# TinyCube01.net
KiCad netlist of a schematic drawn in EAGLE
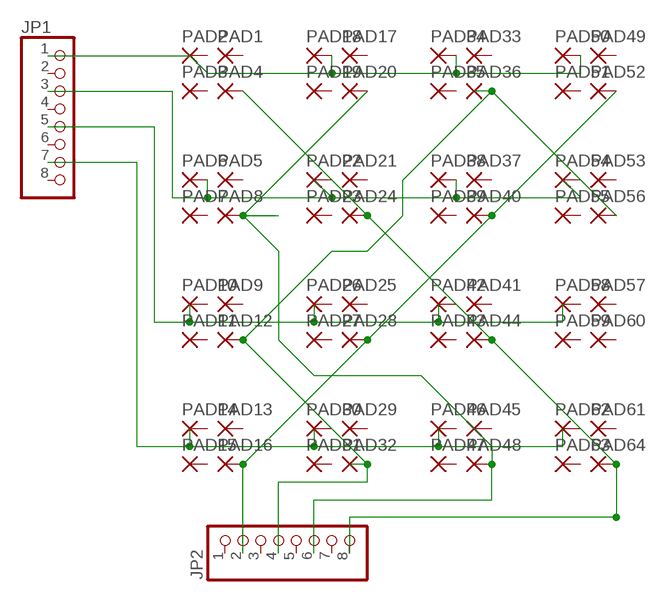
[diagram p0: schematic, sheet 1]

(export (version "E")
  (design (tool "Eeschema 10.0.6"))
  (components
    (comp (ref "JP1")
      (value "PINHD-1X8BIG")
      (footprint "eagle-import:1X08-BIG")
      (libsource (lib "eagle-import") (part "PINHD-1X8BIG"))
    )
    (comp (ref "JP2")
      (value "PINHD-1X8BIG")
      (footprint "eagle-import:1X08-BIG")
      (libsource (lib "eagle-import") (part "PINHD-1X8BIG"))
    )
    (comp (ref "PAD1")
      (value "SMALLPADTHROUGH-HOLE-SMALL")
      (footprint "eagle-import:SMALLPAD")
      (libsource (lib "eagle-import") (part "SMALLPADTHROUGH-HOLE-SMALL"))
    )
    (comp (ref "PAD2")
      (value "SMALLPADTHROUGH-HOLE-SMALL")
      (footprint "eagle-import:SMALLPAD")
      (libsource (lib "eagle-import") (part "SMALLPADTHROUGH-HOLE-SMALL"))
    )
    (comp (ref "PAD3")
      (value "SMALLPADTHROUGH-HOLE-SMALL")
      (footprint "eagle-import:SMALLPAD")
      (libsource (lib "eagle-import") (part "SMALLPADTHROUGH-HOLE-SMALL"))
    )
    (comp (ref "PAD4")
      (value "SMALLPADTHROUGH-HOLE-SMALL")
      (footprint "eagle-import:SMALLPAD")
      (libsource (lib "eagle-import") (part "SMALLPADTHROUGH-HOLE-SMALL"))
    )
    (comp (ref "PAD5")
      (value "SMALLPADTHROUGH-HOLE-SMALL")
      (footprint "eagle-import:SMALLPAD")
      (libsource (lib "eagle-import") (part "SMALLPADTHROUGH-HOLE-SMALL"))
    )
    (comp (ref "PAD6")
      (value "SMALLPADTHROUGH-HOLE-SMALL")
      (footprint "eagle-import:SMALLPAD")
      (libsource (lib "eagle-import") (part "SMALLPADTHROUGH-HOLE-SMALL"))
    )
    (comp (ref "PAD7")
      (value "SMALLPADTHROUGH-HOLE-SMALL")
      (footprint "eagle-import:SMALLPAD")
      (libsource (lib "eagle-import") (part "SMALLPADTHROUGH-HOLE-SMALL"))
    )
    (comp (ref "PAD8")
      (value "SMALLPADTHROUGH-HOLE-SMALL")
      (footprint "eagle-import:SMALLPAD")
      (libsource (lib "eagle-import") (part "SMALLPADTHROUGH-HOLE-SMALL"))
    )
    (comp (ref "PAD9")
      (value "SMALLPADTHROUGH-HOLE-SMALL")
      (footprint "eagle-import:SMALLPAD")
      (libsource (lib "eagle-import") (part "SMALLPADTHROUGH-HOLE-SMALL"))
    )
    (comp (ref "PAD10")
      (value "SMALLPADTHROUGH-HOLE-SMALL")
      (footprint "eagle-import:SMALLPAD")
      (libsource (lib "eagle-import") (part "SMALLPADTHROUGH-HOLE-SMALL"))
    )
    (comp (ref "PAD11")
      (value "SMALLPADTHROUGH-HOLE-SMALL")
      (footprint "eagle-import:SMALLPAD")
      (libsource (lib "eagle-import") (part "SMALLPADTHROUGH-HOLE-SMALL"))
    )
    (comp (ref "PAD12")
      (value "SMALLPADTHROUGH-HOLE-SMALL")
      (footprint "eagle-import:SMALLPAD")
      (libsource (lib "eagle-import") (part "SMALLPADTHROUGH-HOLE-SMALL"))
    )
    (comp (ref "PAD13")
      (value "SMALLPADTHROUGH-HOLE-SMALL")
      (footprint "eagle-import:SMALLPAD")
      (libsource (lib "eagle-import") (part "SMALLPADTHROUGH-HOLE-SMALL"))
    )
    (comp (ref "PAD14")
      (value "SMALLPADTHROUGH-HOLE-SMALL")
      (footprint "eagle-import:SMALLPAD")
      (libsource (lib "eagle-import") (part "SMALLPADTHROUGH-HOLE-SMALL"))
    )
    (comp (ref "PAD15")
      (value "SMALLPADTHROUGH-HOLE-SMALL")
      (footprint "eagle-import:SMALLPAD")
      (libsource (lib "eagle-import") (part "SMALLPADTHROUGH-HOLE-SMALL"))
    )
    (comp (ref "PAD16")
      (value "SMALLPADTHROUGH-HOLE-SMALL")
      (footprint "eagle-import:SMALLPAD")
      (libsource (lib "eagle-import") (part "SMALLPADTHROUGH-HOLE-SMALL"))
    )
    (comp (ref "PAD17")
      (value "SMALLPADTHROUGH-HOLE-SMALL")
      (footprint "eagle-import:SMALLPAD")
      (libsource (lib "eagle-import") (part "SMALLPADTHROUGH-HOLE-SMALL"))
    )
    (comp (ref "PAD18")
      (value "SMALLPADTHROUGH-HOLE-SMALL")
      (footprint "eagle-import:SMALLPAD")
      (libsource (lib "eagle-import") (part "SMALLPADTHROUGH-HOLE-SMALL"))
    )
    (comp (ref "PAD19")
      (value "SMALLPADTHROUGH-HOLE-SMALL")
      (footprint "eagle-import:SMALLPAD")
      (libsource (lib "eagle-import") (part "SMALLPADTHROUGH-HOLE-SMALL"))
    )
    (comp (ref "PAD20")
      (value "SMALLPADTHROUGH-HOLE-SMALL")
      (footprint "eagle-import:SMALLPAD")
      (libsource (lib "eagle-import") (part "SMALLPADTHROUGH-HOLE-SMALL"))
    )
    (comp (ref "PAD21")
      (value "SMALLPADTHROUGH-HOLE-SMALL")
      (footprint "eagle-import:SMALLPAD")
      (libsource (lib "eagle-import") (part "SMALLPADTHROUGH-HOLE-SMALL"))
    )
    (comp (ref "PAD22")
      (value "SMALLPADTHROUGH-HOLE-SMALL")
      (footprint "eagle-import:SMALLPAD")
      (libsource (lib "eagle-import") (part "SMALLPADTHROUGH-HOLE-SMALL"))
    )
    (comp (ref "PAD23")
      (value "SMALLPADTHROUGH-HOLE-SMALL")
      (footprint "eagle-import:SMALLPAD")
      (libsource (lib "eagle-import") (part "SMALLPADTHROUGH-HOLE-SMALL"))
    )
    (comp (ref "PAD24")
      (value "SMALLPADTHROUGH-HOLE-SMALL")
      (footprint "eagle-import:SMALLPAD")
      (libsource (lib "eagle-import") (part "SMALLPADTHROUGH-HOLE-SMALL"))
    )
    (comp (ref "PAD25")
      (value "SMALLPADTHROUGH-HOLE-SMALL")
      (footprint "eagle-import:SMALLPAD")
      (libsource (lib "eagle-import") (part "SMALLPADTHROUGH-HOLE-SMALL"))
    )
    (comp (ref "PAD26")
      (value "SMALLPADTHROUGH-HOLE-SMALL")
      (footprint "eagle-import:SMALLPAD")
      (libsource (lib "eagle-import") (part "SMALLPADTHROUGH-HOLE-SMALL"))
    )
    (comp (ref "PAD27")
      (value "SMALLPADTHROUGH-HOLE-SMALL")
      (footprint "eagle-import:SMALLPAD")
      (libsource (lib "eagle-import") (part "SMALLPADTHROUGH-HOLE-SMALL"))
    )
    (comp (ref "PAD28")
      (value "SMALLPADTHROUGH-HOLE-SMALL")
      (footprint "eagle-import:SMALLPAD")
      (libsource (lib "eagle-import") (part "SMALLPADTHROUGH-HOLE-SMALL"))
    )
    (comp (ref "PAD29")
      (value "SMALLPADTHROUGH-HOLE-SMALL")
      (footprint "eagle-import:SMALLPAD")
      (libsource (lib "eagle-import") (part "SMALLPADTHROUGH-HOLE-SMALL"))
    )
    (comp (ref "PAD30")
      (value "SMALLPADTHROUGH-HOLE-SMALL")
      (footprint "eagle-import:SMALLPAD")
      (libsource (lib "eagle-import") (part "SMALLPADTHROUGH-HOLE-SMALL"))
    )
    (comp (ref "PAD31")
      (value "SMALLPADTHROUGH-HOLE-SMALL")
      (footprint "eagle-import:SMALLPAD")
      (libsource (lib "eagle-import") (part "SMALLPADTHROUGH-HOLE-SMALL"))
    )
    (comp (ref "PAD32")
      (value "SMALLPADTHROUGH-HOLE-SMALL")
      (footprint "eagle-import:SMALLPAD")
      (libsource (lib "eagle-import") (part "SMALLPADTHROUGH-HOLE-SMALL"))
    )
    (comp (ref "PAD33")
      (value "SMALLPADTHROUGH-HOLE-SMALL")
      (footprint "eagle-import:SMALLPAD")
      (libsource (lib "eagle-import") (part "SMALLPADTHROUGH-HOLE-SMALL"))
    )
    (comp (ref "PAD34")
      (value "SMALLPADTHROUGH-HOLE-SMALL")
      (footprint "eagle-import:SMALLPAD")
      (libsource (lib "eagle-import") (part "SMALLPADTHROUGH-HOLE-SMALL"))
    )
    (comp (ref "PAD35")
      (value "SMALLPADTHROUGH-HOLE-SMALL")
      (footprint "eagle-import:SMALLPAD")
      (libsource (lib "eagle-import") (part "SMALLPADTHROUGH-HOLE-SMALL"))
    )
    (comp (ref "PAD36")
      (value "SMALLPADTHROUGH-HOLE-SMALL")
      (footprint "eagle-import:SMALLPAD")
      (libsource (lib "eagle-import") (part "SMALLPADTHROUGH-HOLE-SMALL"))
    )
    (comp (ref "PAD37")
      (value "SMALLPADTHROUGH-HOLE-SMALL")
      (footprint "eagle-import:SMALLPAD")
      (libsource (lib "eagle-import") (part "SMALLPADTHROUGH-HOLE-SMALL"))
    )
    (comp (ref "PAD38")
      (value "SMALLPADTHROUGH-HOLE-SMALL")
      (footprint "eagle-import:SMALLPAD")
      (libsource (lib "eagle-import") (part "SMALLPADTHROUGH-HOLE-SMALL"))
    )
    (comp (ref "PAD39")
      (value "SMALLPADTHROUGH-HOLE-SMALL")
      (footprint "eagle-import:SMALLPAD")
      (libsource (lib "eagle-import") (part "SMALLPADTHROUGH-HOLE-SMALL"))
    )
    (comp (ref "PAD40")
      (value "SMALLPADTHROUGH-HOLE-SMALL")
      (footprint "eagle-import:SMALLPAD")
      (libsource (lib "eagle-import") (part "SMALLPADTHROUGH-HOLE-SMALL"))
    )
    (comp (ref "PAD41")
      (value "SMALLPADTHROUGH-HOLE-SMALL")
      (footprint "eagle-import:SMALLPAD")
      (libsource (lib "eagle-import") (part "SMALLPADTHROUGH-HOLE-SMALL"))
    )
    (comp (ref "PAD42")
      (value "SMALLPADTHROUGH-HOLE-SMALL")
      (footprint "eagle-import:SMALLPAD")
      (libsource (lib "eagle-import") (part "SMALLPADTHROUGH-HOLE-SMALL"))
    )
    (comp (ref "PAD43")
      (value "SMALLPADTHROUGH-HOLE-SMALL")
      (footprint "eagle-import:SMALLPAD")
      (libsource (lib "eagle-import") (part "SMALLPADTHROUGH-HOLE-SMALL"))
    )
    (comp (ref "PAD44")
      (value "SMALLPADTHROUGH-HOLE-SMALL")
      (footprint "eagle-import:SMALLPAD")
      (libsource (lib "eagle-import") (part "SMALLPADTHROUGH-HOLE-SMALL"))
    )
    (comp (ref "PAD45")
      (value "SMALLPADTHROUGH-HOLE-SMALL")
      (footprint "eagle-import:SMALLPAD")
      (libsource (lib "eagle-import") (part "SMALLPADTHROUGH-HOLE-SMALL"))
    )
    (comp (ref "PAD46")
      (value "SMALLPADTHROUGH-HOLE-SMALL")
      (footprint "eagle-import:SMALLPAD")
      (libsource (lib "eagle-import") (part "SMALLPADTHROUGH-HOLE-SMALL"))
    )
    (comp (ref "PAD47")
      (value "SMALLPADTHROUGH-HOLE-SMALL")
      (footprint "eagle-import:SMALLPAD")
      (libsource (lib "eagle-import") (part "SMALLPADTHROUGH-HOLE-SMALL"))
    )
    (comp (ref "PAD48")
      (value "SMALLPADTHROUGH-HOLE-SMALL")
      (footprint "eagle-import:SMALLPAD")
      (libsource (lib "eagle-import") (part "SMALLPADTHROUGH-HOLE-SMALL"))
    )
    (comp (ref "PAD49")
      (value "SMALLPADTHROUGH-HOLE-SMALL")
      (footprint "eagle-import:SMALLPAD")
      (libsource (lib "eagle-import") (part "SMALLPADTHROUGH-HOLE-SMALL"))
    )
    (comp (ref "PAD50")
      (value "SMALLPADTHROUGH-HOLE-SMALL")
      (footprint "eagle-import:SMALLPAD")
      (libsource (lib "eagle-import") (part "SMALLPADTHROUGH-HOLE-SMALL"))
    )
    (comp (ref "PAD51")
      (value "SMALLPADTHROUGH-HOLE-SMALL")
      (footprint "eagle-import:SMALLPAD")
      (libsource (lib "eagle-import") (part "SMALLPADTHROUGH-HOLE-SMALL"))
    )
    (comp (ref "PAD52")
      (value "SMALLPADTHROUGH-HOLE-SMALL")
      (footprint "eagle-import:SMALLPAD")
      (libsource (lib "eagle-import") (part "SMALLPADTHROUGH-HOLE-SMALL"))
    )
    (comp (ref "PAD53")
      (value "SMALLPADTHROUGH-HOLE-SMALL")
      (footprint "eagle-import:SMALLPAD")
      (libsource (lib "eagle-import") (part "SMALLPADTHROUGH-HOLE-SMALL"))
    )
    (comp (ref "PAD54")
      (value "SMALLPADTHROUGH-HOLE-SMALL")
      (footprint "eagle-import:SMALLPAD")
      (libsource (lib "eagle-import") (part "SMALLPADTHROUGH-HOLE-SMALL"))
    )
    (comp (ref "PAD55")
      (value "SMALLPADTHROUGH-HOLE-SMALL")
      (footprint "eagle-import:SMALLPAD")
      (libsource (lib "eagle-import") (part "SMALLPADTHROUGH-HOLE-SMALL"))
    )
    (comp (ref "PAD56")
      (value "SMALLPADTHROUGH-HOLE-SMALL")
      (footprint "eagle-import:SMALLPAD")
      (libsource (lib "eagle-import") (part "SMALLPADTHROUGH-HOLE-SMALL"))
    )
    (comp (ref "PAD57")
      (value "SMALLPADTHROUGH-HOLE-SMALL")
      (footprint "eagle-import:SMALLPAD")
      (libsource (lib "eagle-import") (part "SMALLPADTHROUGH-HOLE-SMALL"))
    )
    (comp (ref "PAD58")
      (value "SMALLPADTHROUGH-HOLE-SMALL")
      (footprint "eagle-import:SMALLPAD")
      (libsource (lib "eagle-import") (part "SMALLPADTHROUGH-HOLE-SMALL"))
    )
    (comp (ref "PAD59")
      (value "SMALLPADTHROUGH-HOLE-SMALL")
      (footprint "eagle-import:SMALLPAD")
      (libsource (lib "eagle-import") (part "SMALLPADTHROUGH-HOLE-SMALL"))
    )
    (comp (ref "PAD60")
      (value "SMALLPADTHROUGH-HOLE-SMALL")
      (footprint "eagle-import:SMALLPAD")
      (libsource (lib "eagle-import") (part "SMALLPADTHROUGH-HOLE-SMALL"))
    )
    (comp (ref "PAD61")
      (value "SMALLPADTHROUGH-HOLE-SMALL")
      (footprint "eagle-import:SMALLPAD")
      (libsource (lib "eagle-import") (part "SMALLPADTHROUGH-HOLE-SMALL"))
    )
    (comp (ref "PAD62")
      (value "SMALLPADTHROUGH-HOLE-SMALL")
      (footprint "eagle-import:SMALLPAD")
      (libsource (lib "eagle-import") (part "SMALLPADTHROUGH-HOLE-SMALL"))
    )
    (comp (ref "PAD63")
      (value "SMALLPADTHROUGH-HOLE-SMALL")
      (footprint "eagle-import:SMALLPAD")
      (libsource (lib "eagle-import") (part "SMALLPADTHROUGH-HOLE-SMALL"))
    )
    (comp (ref "PAD64")
      (value "SMALLPADTHROUGH-HOLE-SMALL")
      (footprint "eagle-import:SMALLPAD")
      (libsource (lib "eagle-import") (part "SMALLPADTHROUGH-HOLE-SMALL"))
    )
  )
  (nets
    (net (code "1") (name "Net-(PAD12-P)") (class "Default")
      (node (ref "JP2") (pin "4") (pinfunction "4_4") (pintype "passive"))
      (node (ref "PAD12") (pin "1") (pinfunction "P_1") (pintype "passive"))
      (node (ref "PAD32") (pin "1") (pinfunction "P_1") (pintype "passive"))
      (node (ref "PAD36") (pin "1") (pinfunction "P_1") (pintype "passive"))
      (node (ref "PAD56") (pin "1") (pinfunction "P_1") (pintype "passive"))
    )
    (net (code "2") (name "Net-(PAD16-P)") (class "Default")
      (node (ref "JP2") (pin "2") (pinfunction "2_2") (pintype "passive"))
      (node (ref "PAD16") (pin "1") (pinfunction "P_1") (pintype "passive"))
      (node (ref "PAD28") (pin "1") (pinfunction "P_1") (pintype "passive"))
      (node (ref "PAD40") (pin "1") (pinfunction "P_1") (pintype "passive"))
      (node (ref "PAD52") (pin "1") (pinfunction "P_1") (pintype "passive"))
    )
    (net (code "3") (name "Net-(PAD18-P)") (class "Default")
      (node (ref "JP1") (pin "1") (pinfunction "1_1") (pintype "passive"))
      (node (ref "PAD18") (pin "1") (pinfunction "P_1") (pintype "passive"))
      (node (ref "PAD34") (pin "1") (pinfunction "P_1") (pintype "passive"))
      (node (ref "PAD50") (pin "1") (pinfunction "P_1") (pintype "passive"))
    )
    (net (code "4") (name "Net-(PAD20-P)") (class "Default")
      (node (ref "JP2") (pin "6") (pinfunction "6_6") (pintype "passive"))
      (node (ref "PAD20") (pin "1") (pinfunction "P_1") (pintype "passive"))
      (node (ref "PAD48") (pin "1") (pinfunction "P_1") (pintype "passive"))
      (node (ref "PAD8") (pin "1") (pinfunction "P_1") (pintype "passive"))
    )
    (net (code "5") (name "Net-(PAD24-P)") (class "Default")
      (node (ref "JP2") (pin "8") (pinfunction "8_8") (pintype "passive"))
      (node (ref "PAD24") (pin "1") (pinfunction "P_1") (pintype "passive"))
      (node (ref "PAD4") (pin "1") (pinfunction "P_1") (pintype "passive"))
      (node (ref "PAD44") (pin "1") (pinfunction "P_1") (pintype "passive"))
      (node (ref "PAD64") (pin "1") (pinfunction "P_1") (pintype "passive"))
    )
    (net (code "6") (name "Net-(PAD38-P)") (class "Default")
      (node (ref "JP1") (pin "3") (pinfunction "3_3") (pintype "passive"))
      (node (ref "PAD38") (pin "1") (pinfunction "P_1") (pintype "passive"))
      (node (ref "PAD6") (pin "1") (pinfunction "P_1") (pintype "passive"))
    )
    (net (code "7") (name "unconnected-(JP1-Pad2)") (class "Default")
      (node (ref "JP1") (pin "2") (pinfunction "2_2") (pintype "passive"))
    )
    (net (code "8") (name "unconnected-(JP1-Pad4)") (class "Default")
      (node (ref "JP1") (pin "4") (pinfunction "4_4") (pintype "passive"))
    )
    (net (code "9") (name "unconnected-(JP1-Pad5)") (class "Default")
      (node (ref "JP1") (pin "5") (pinfunction "5_5") (pintype "passive"))
    )
    (net (code "10") (name "unconnected-(JP1-Pad6)") (class "Default")
      (node (ref "JP1") (pin "6") (pinfunction "6_6") (pintype "passive"))
    )
    (net (code "11") (name "unconnected-(JP1-Pad7)") (class "Default")
      (node (ref "JP1") (pin "7") (pinfunction "7_7") (pintype "passive"))
    )
    (net (code "12") (name "unconnected-(JP1-Pad8)") (class "Default")
      (node (ref "JP1") (pin "8") (pinfunction "8_8") (pintype "passive"))
    )
    (net (code "13") (name "unconnected-(JP2-Pad1)") (class "Default")
      (node (ref "JP2") (pin "1") (pinfunction "1_1") (pintype "passive"))
    )
    (net (code "14") (name "unconnected-(JP2-Pad3)") (class "Default")
      (node (ref "JP2") (pin "3") (pinfunction "3_3") (pintype "passive"))
    )
    (net (code "15") (name "unconnected-(JP2-Pad5)") (class "Default")
      (node (ref "JP2") (pin "5") (pinfunction "5_5") (pintype "passive"))
    )
    (net (code "16") (name "unconnected-(JP2-Pad7)") (class "Default")
      (node (ref "JP2") (pin "7") (pinfunction "7_7") (pintype "passive"))
    )
    (net (code "17") (name "unconnected-(PAD1-P-Pad1)") (class "Default")
      (node (ref "PAD1") (pin "1") (pinfunction "P_1") (pintype "passive"))
    )
    (net (code "18") (name "unconnected-(PAD2-P-Pad1)") (class "Default")
      (node (ref "PAD2") (pin "1") (pinfunction "P_1") (pintype "passive"))
    )
    (net (code "19") (name "unconnected-(PAD3-P-Pad1)") (class "Default")
      (node (ref "PAD3") (pin "1") (pinfunction "P_1") (pintype "passive"))
    )
    (net (code "20") (name "unconnected-(PAD5-P-Pad1)") (class "Default")
      (node (ref "PAD5") (pin "1") (pinfunction "P_1") (pintype "passive"))
    )
    (net (code "21") (name "unconnected-(PAD7-P-Pad1)") (class "Default")
      (node (ref "PAD7") (pin "1") (pinfunction "P_1") (pintype "passive"))
    )
    (net (code "22") (name "unconnected-(PAD9-P-Pad1)") (class "Default")
      (node (ref "PAD9") (pin "1") (pinfunction "P_1") (pintype "passive"))
    )
    (net (code "23") (name "unconnected-(PAD10-P-Pad1)") (class "Default")
      (node (ref "PAD10") (pin "1") (pinfunction "P_1") (pintype "passive"))
    )
    (net (code "24") (name "unconnected-(PAD11-P-Pad1)") (class "Default")
      (node (ref "PAD11") (pin "1") (pinfunction "P_1") (pintype "passive"))
    )
    (net (code "25") (name "unconnected-(PAD13-P-Pad1)") (class "Default")
      (node (ref "PAD13") (pin "1") (pinfunction "P_1") (pintype "passive"))
    )
    (net (code "26") (name "unconnected-(PAD14-P-Pad1)") (class "Default")
      (node (ref "PAD14") (pin "1") (pinfunction "P_1") (pintype "passive"))
    )
    (net (code "27") (name "unconnected-(PAD15-P-Pad1)") (class "Default")
      (node (ref "PAD15") (pin "1") (pinfunction "P_1") (pintype "passive"))
    )
    (net (code "28") (name "unconnected-(PAD17-P-Pad1)") (class "Default")
      (node (ref "PAD17") (pin "1") (pinfunction "P_1") (pintype "passive"))
    )
    (net (code "29") (name "unconnected-(PAD19-P-Pad1)") (class "Default")
      (node (ref "PAD19") (pin "1") (pinfunction "P_1") (pintype "passive"))
    )
    (net (code "30") (name "unconnected-(PAD21-P-Pad1)") (class "Default")
      (node (ref "PAD21") (pin "1") (pinfunction "P_1") (pintype "passive"))
    )
    (net (code "31") (name "unconnected-(PAD22-P-Pad1)") (class "Default")
      (node (ref "PAD22") (pin "1") (pinfunction "P_1") (pintype "passive"))
    )
    (net (code "32") (name "unconnected-(PAD23-P-Pad1)") (class "Default")
      (node (ref "PAD23") (pin "1") (pinfunction "P_1") (pintype "passive"))
    )
    (net (code "33") (name "unconnected-(PAD25-P-Pad1)") (class "Default")
      (node (ref "PAD25") (pin "1") (pinfunction "P_1") (pintype "passive"))
    )
    (net (code "34") (name "unconnected-(PAD26-P-Pad1)") (class "Default")
      (node (ref "PAD26") (pin "1") (pinfunction "P_1") (pintype "passive"))
    )
    (net (code "35") (name "unconnected-(PAD27-P-Pad1)") (class "Default")
      (node (ref "PAD27") (pin "1") (pinfunction "P_1") (pintype "passive"))
    )
    (net (code "36") (name "unconnected-(PAD29-P-Pad1)") (class "Default")
      (node (ref "PAD29") (pin "1") (pinfunction "P_1") (pintype "passive"))
    )
    (net (code "37") (name "unconnected-(PAD30-P-Pad1)") (class "Default")
      (node (ref "PAD30") (pin "1") (pinfunction "P_1") (pintype "passive"))
    )
    (net (code "38") (name "unconnected-(PAD31-P-Pad1)") (class "Default")
      (node (ref "PAD31") (pin "1") (pinfunction "P_1") (pintype "passive"))
    )
    (net (code "39") (name "unconnected-(PAD33-P-Pad1)") (class "Default")
      (node (ref "PAD33") (pin "1") (pinfunction "P_1") (pintype "passive"))
    )
    (net (code "40") (name "unconnected-(PAD35-P-Pad1)") (class "Default")
      (node (ref "PAD35") (pin "1") (pinfunction "P_1") (pintype "passive"))
    )
    (net (code "41") (name "unconnected-(PAD37-P-Pad1)") (class "Default")
      (node (ref "PAD37") (pin "1") (pinfunction "P_1") (pintype "passive"))
    )
    (net (code "42") (name "unconnected-(PAD39-P-Pad1)") (class "Default")
      (node (ref "PAD39") (pin "1") (pinfunction "P_1") (pintype "passive"))
    )
    (net (code "43") (name "unconnected-(PAD41-P-Pad1)") (class "Default")
      (node (ref "PAD41") (pin "1") (pinfunction "P_1") (pintype "passive"))
    )
    (net (code "44") (name "unconnected-(PAD42-P-Pad1)") (class "Default")
      (node (ref "PAD42") (pin "1") (pinfunction "P_1") (pintype "passive"))
    )
    (net (code "45") (name "unconnected-(PAD43-P-Pad1)") (class "Default")
      (node (ref "PAD43") (pin "1") (pinfunction "P_1") (pintype "passive"))
    )
    (net (code "46") (name "unconnected-(PAD45-P-Pad1)") (class "Default")
      (node (ref "PAD45") (pin "1") (pinfunction "P_1") (pintype "passive"))
    )
    (net (code "47") (name "unconnected-(PAD46-P-Pad1)") (class "Default")
      (node (ref "PAD46") (pin "1") (pinfunction "P_1") (pintype "passive"))
    )
    (net (code "48") (name "unconnected-(PAD47-P-Pad1)") (class "Default")
      (node (ref "PAD47") (pin "1") (pinfunction "P_1") (pintype "passive"))
    )
    (net (code "49") (name "unconnected-(PAD49-P-Pad1)") (class "Default")
      (node (ref "PAD49") (pin "1") (pinfunction "P_1") (pintype "passive"))
    )
    (net (code "50") (name "unconnected-(PAD51-P-Pad1)") (class "Default")
      (node (ref "PAD51") (pin "1") (pinfunction "P_1") (pintype "passive"))
    )
    (net (code "51") (name "unconnected-(PAD53-P-Pad1)") (class "Default")
      (node (ref "PAD53") (pin "1") (pinfunction "P_1") (pintype "passive"))
    )
    (net (code "52") (name "unconnected-(PAD54-P-Pad1)") (class "Default")
      (node (ref "PAD54") (pin "1") (pinfunction "P_1") (pintype "passive"))
    )
    (net (code "53") (name "unconnected-(PAD55-P-Pad1)") (class "Default")
      (node (ref "PAD55") (pin "1") (pinfunction "P_1") (pintype "passive"))
    )
    (net (code "54") (name "unconnected-(PAD57-P-Pad1)") (class "Default")
      (node (ref "PAD57") (pin "1") (pinfunction "P_1") (pintype "passive"))
    )
    (net (code "55") (name "unconnected-(PAD58-P-Pad1)") (class "Default")
      (node (ref "PAD58") (pin "1") (pinfunction "P_1") (pintype "passive"))
    )
    (net (code "56") (name "unconnected-(PAD59-P-Pad1)") (class "Default")
      (node (ref "PAD59") (pin "1") (pinfunction "P_1") (pintype "passive"))
    )
    (net (code "57") (name "unconnected-(PAD60-P-Pad1)") (class "Default")
      (node (ref "PAD60") (pin "1") (pinfunction "P_1") (pintype "passive"))
    )
    (net (code "58") (name "unconnected-(PAD61-P-Pad1)") (class "Default")
      (node (ref "PAD61") (pin "1") (pinfunction "P_1") (pintype "passive"))
    )
    (net (code "59") (name "unconnected-(PAD62-P-Pad1)") (class "Default")
      (node (ref "PAD62") (pin "1") (pinfunction "P_1") (pintype "passive"))
    )
    (net (code "60") (name "unconnected-(PAD63-P-Pad1)") (class "Default")
      (node (ref "PAD63") (pin "1") (pinfunction "P_1") (pintype "passive"))
    )
  )
)
